# fonte.net
KiCad netlist of a schematic drawn in EAGLE
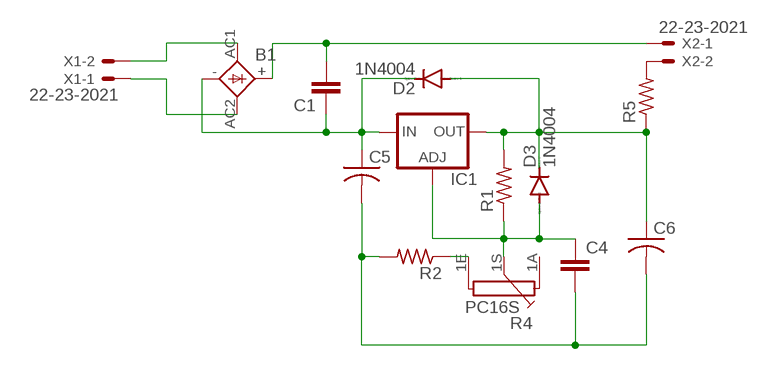
[diagram p0: schematic, sheet 1]

(export (version "E")
  (design (tool "Eeschema 10.0.6"))
  (components
    (comp (ref "B1")
      (value "2KBB-R")
      (footprint "eagle-import:2KBB-R")
      (libsource (lib "eagle-import") (part "2KBB-R"))
    )
    (comp (ref "C1")
      (value "C2,5-3")
      (footprint "eagle-import:C2.5-3")
      (libsource (lib "eagle-import") (part "C2,5-3"))
    )
    (comp (ref "C4")
      (value "C2.5/2")
      (footprint "eagle-import:C2.5-2")
      (libsource (lib "eagle-import") (part "C2.5/2"))
    )
    (comp (ref "C5")
      (value "C-US025-024X044")
      (footprint "eagle-import:C025-024X044")
      (libsource (lib "eagle-import") (part "C-US025-024X044"))
    )
    (comp (ref "C6")
      (value "C-US025-024X044")
      (footprint "eagle-import:C025-024X044")
      (libsource (lib "eagle-import") (part "C-US025-024X044"))
    )
    (comp (ref "D2")
      (value "1N4004")
      (footprint "eagle-import:DO41-10")
      (libsource (lib "eagle-import") (part "1N4004"))
    )
    (comp (ref "D3")
      (value "1N4004")
      (footprint "eagle-import:DO41-10")
      (libsource (lib "eagle-import") (part "1N4004"))
    )
    (comp (ref "IC1")
      (value "LM317L")
      (footprint "eagle-import:317L")
      (libsource (lib "eagle-import") (part "LM317L"))
    )
    (comp (ref "R1")
      (value "R-US_0204/7")
      (footprint "eagle-import:0204_7")
      (libsource (lib "eagle-import") (part "R-US_0204/7"))
    )
    (comp (ref "R2")
      (value "R-US_0204/7")
      (footprint "eagle-import:0204_7")
      (libsource (lib "eagle-import") (part "R-US_0204/7"))
    )
    (comp (ref "R4")
      (value "PC16S")
      (footprint "eagle-import:PC16S")
      (libsource (lib "eagle-import") (part "PC16S"))
    )
    (comp (ref "R5")
      (value "R-US_0204/7")
      (footprint "eagle-import:0204_7")
      (libsource (lib "eagle-import") (part "R-US_0204/7"))
    )
    (comp (ref "X1")
      (value "22-23-2021")
      (footprint "eagle-import:22-23-2021")
      (fields (field (name "MF") "MOLEX"))
      (libsource (lib "eagle-import") (part "22-23-2021"))
    )
    (comp (ref "X2")
      (value "22-23-2021")
      (footprint "eagle-import:22-23-2021")
      (fields (field (name "MF") "MOLEX"))
      (libsource (lib "eagle-import") (part "22-23-2021"))
    )
  )
  (nets
    (net (code "1") (name "Net-(C4-Pad2)") (class "Default")
      (node (ref "C4") (pin "2") (pinfunction "2_2") (pintype "passive"))
      (node (ref "C5") (pin "2") (pinfunction "2_2") (pintype "passive"))
      (node (ref "C6") (pin "2") (pinfunction "2_2") (pintype "passive"))
      (node (ref "R2") (pin "2") (pinfunction "2_2") (pintype "passive"))
    )
    (net (code "2") (name "Net-(IC1-ADJ)") (class "Default")
      (node (ref "C4") (pin "1") (pinfunction "1_1") (pintype "passive"))
      (node (ref "D3") (pin "A") (pinfunction "A_A") (pintype "passive"))
      (node (ref "IC1") (pin "1") (pinfunction "ADJ_1") (pintype "input"))
      (node (ref "R1") (pin "1") (pinfunction "1_1") (pintype "passive"))
      (node (ref "R4") (pin "1S") (pinfunction "1S_1S") (pintype "passive"))
    )
    (net (code "3") (name "Net-(IC1-IN)") (class "Default")
      (node (ref "B1") (pin "-") (pinfunction "-_-") (pintype "passive"))
      (node (ref "C1") (pin "1") (pinfunction "1_1") (pintype "passive"))
      (node (ref "C5") (pin "1") (pinfunction "1_1") (pintype "passive"))
      (node (ref "D2") (pin "C") (pinfunction "C_C") (pintype "passive"))
      (node (ref "IC1") (pin "3") (pinfunction "IN_3") (pintype "input"))
    )
    (net (code "4") (name "Net-(IC1-OUT)") (class "Default")
      (node (ref "C6") (pin "1") (pinfunction "1_1") (pintype "passive"))
      (node (ref "D2") (pin "A") (pinfunction "A_A") (pintype "passive"))
      (node (ref "D3") (pin "C") (pinfunction "C_C") (pintype "passive"))
      (node (ref "IC1") (pin "2") (pinfunction "OUT_2") (pintype "passive"))
      (node (ref "R1") (pin "2") (pinfunction "2_2") (pintype "passive"))
      (node (ref "R5") (pin "1") (pinfunction "1_1") (pintype "passive"))
    )
    (net (code "5") (name "Net-(R2-Pad1)") (class "Default")
      (node (ref "R2") (pin "1") (pinfunction "1_1") (pintype "passive"))
      (node (ref "R4") (pin "1E") (pinfunction "1E_1E") (pintype "passive"))
    )
    (net (code "6") (name "Net-(X1A-S)") (class "Default")
      (node (ref "B1") (pin "AC2") (pinfunction "AC2_AC2") (pintype "passive"))
      (node (ref "X1") (pin "1") (pinfunction "S_1") (pintype "passive"))
    )
    (net (code "7") (name "Net-(X1B-S)") (class "Default")
      (node (ref "B1") (pin "AC1") (pinfunction "AC1_AC1") (pintype "passive"))
      (node (ref "X1") (pin "2") (pinfunction "S_2") (pintype "passive"))
    )
    (net (code "8") (name "Net-(X2A-S)") (class "Default")
      (node (ref "B1") (pin "+") (pinfunction "+_+") (pintype "passive"))
      (node (ref "C1") (pin "2") (pinfunction "2_2") (pintype "passive"))
      (node (ref "X2") (pin "1") (pinfunction "S_1") (pintype "passive"))
    )
    (net (code "9") (name "Net-(X2B-S)") (class "Default")
      (node (ref "R5") (pin "2") (pinfunction "2_2") (pintype "passive"))
      (node (ref "X2") (pin "2") (pinfunction "S_2") (pintype "passive"))
    )
    (net (code "10") (name "unconnected-(R4-Pad1A)") (class "Default")
      (node (ref "R4") (pin "1A") (pinfunction "1A_1A") (pintype "passive"))
    )
  )
)
